# Extension_CN.net
KiCad netlist of a schematic drawn in Altium Designer
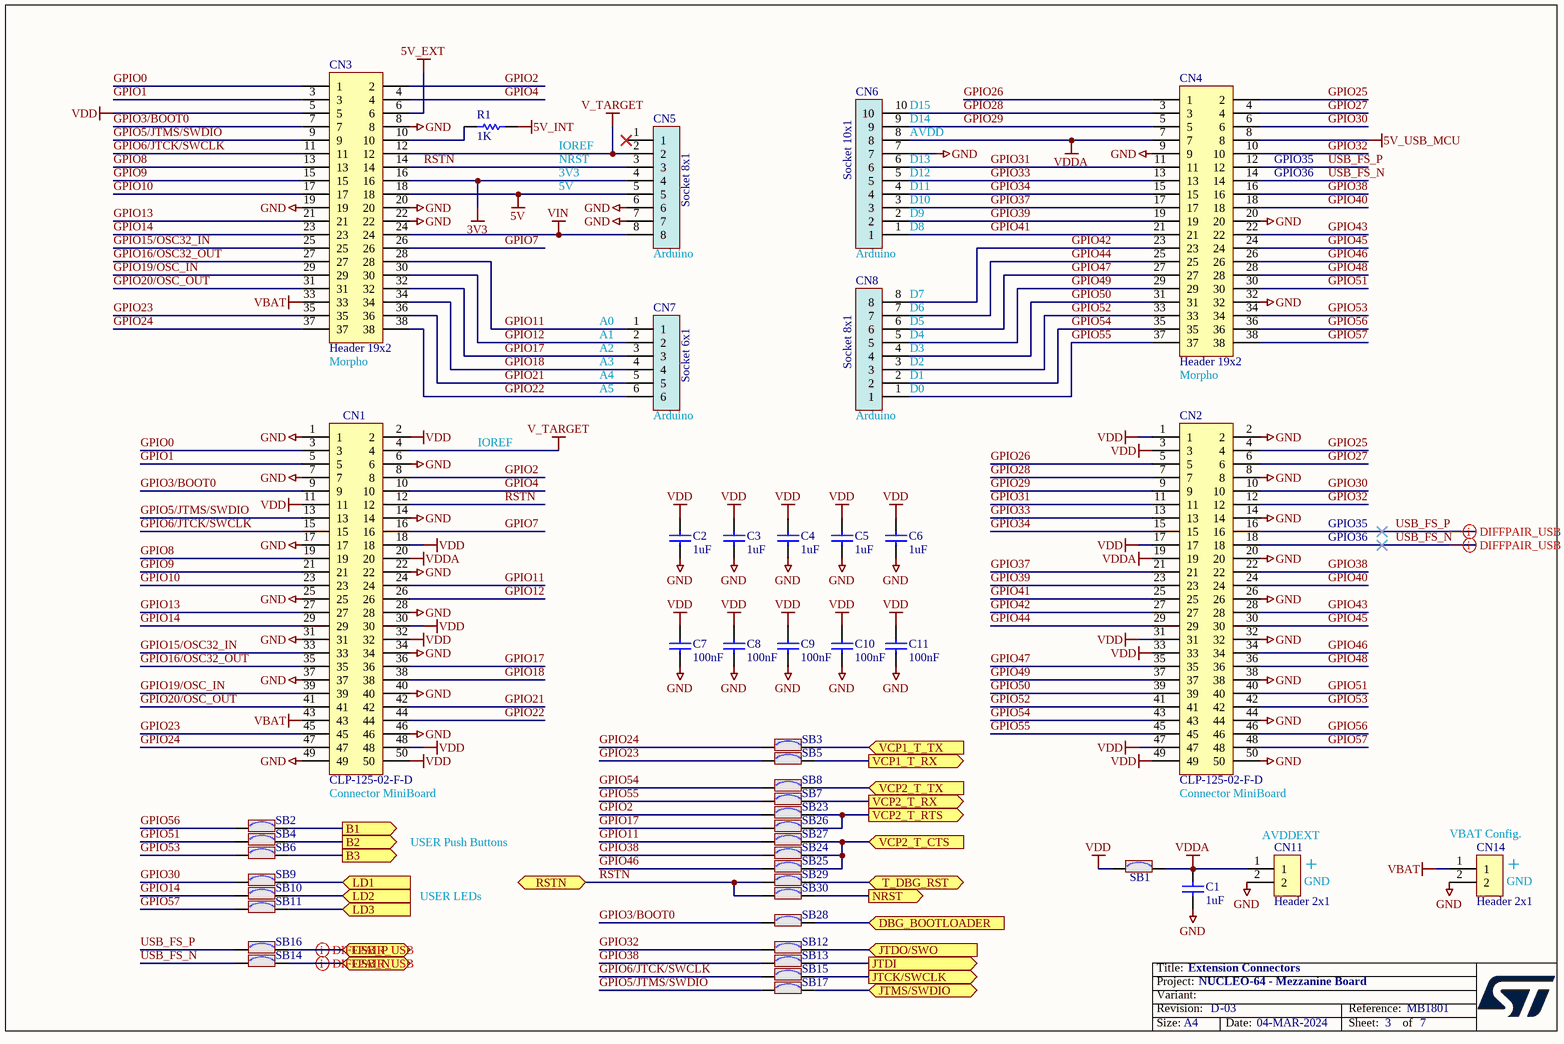
[diagram p0: Extension_CN.SchDoc]

(export (version "E")
  (design (tool "Eeschema 10.0.6"))
  (components
    (comp (ref "C1")
      (value "1uF")
      (footprint "MCD_PARTS:C0805_H0P85")
      (description "Capacitor, MLCC, 1uF, 16V, X5R, +/-10%, 0805, T=0.85mm")
      (fields
        (field (name "INTERNAL_PART_NUMBER") "MCD-01550")
        (field (name "MANUFACTURER_PART_NUMBER") "CC0805KRX5R7BB105")
      )
      (libsource (lib "MCD_PARTS_database") (part "Capacitor"))
    )
    (comp (ref "C2")
      (value "1uF")
      (footprint "MCD_PARTS:C0805_H0P85")
      (description "Capacitor, MLCC, 1uF, 16V, X5R, +/-10%, 0805, T=0.85mm")
      (fields
        (field (name "INTERNAL_PART_NUMBER") "MCD-01550")
        (field (name "MANUFACTURER_PART_NUMBER") "CC0805KRX5R7BB105")
      )
      (libsource (lib "MCD_PARTS_database") (part "Capacitor"))
    )
    (comp (ref "C3")
      (value "1uF")
      (footprint "MCD_PARTS:C0805_H0P85")
      (description "Capacitor, MLCC, 1uF, 16V, X5R, +/-10%, 0805, T=0.85mm")
      (fields
        (field (name "INTERNAL_PART_NUMBER") "MCD-01550")
        (field (name "MANUFACTURER_PART_NUMBER") "CC0805KRX5R7BB105")
      )
      (libsource (lib "MCD_PARTS_database") (part "Capacitor"))
    )
    (comp (ref "C4")
      (value "1uF")
      (footprint "MCD_PARTS:C0805_H0P85")
      (description "Capacitor, MLCC, 1uF, 16V, X5R, +/-10%, 0805, T=0.85mm")
      (fields
        (field (name "INTERNAL_PART_NUMBER") "MCD-01550")
        (field (name "MANUFACTURER_PART_NUMBER") "CC0805KRX5R7BB105")
      )
      (libsource (lib "MCD_PARTS_database") (part "Capacitor"))
    )
    (comp (ref "C5")
      (value "1uF")
      (footprint "MCD_PARTS:C0805_H0P85")
      (description "Capacitor, MLCC, 1uF, 16V, X5R, +/-10%, 0805, T=0.85mm")
      (fields
        (field (name "INTERNAL_PART_NUMBER") "MCD-01550")
        (field (name "MANUFACTURER_PART_NUMBER") "CC0805KRX5R7BB105")
      )
      (libsource (lib "MCD_PARTS_database") (part "Capacitor"))
    )
    (comp (ref "C6")
      (value "1uF")
      (footprint "MCD_PARTS:C0805_H0P85")
      (description "Capacitor, MLCC, 1uF, 16V, X5R, +/-10%, 0805, T=0.85mm")
      (fields
        (field (name "INTERNAL_PART_NUMBER") "MCD-01550")
        (field (name "MANUFACTURER_PART_NUMBER") "CC0805KRX5R7BB105")
      )
      (libsource (lib "MCD_PARTS_database") (part "Capacitor"))
    )
    (comp (ref "C7")
      (value "100nF")
      (footprint "MCD_PARTS:C0402")
      (description "Capacitor, MLCC, 100nF, 25V, X7R, +/-10%, 0402, T=0.5mm")
      (fields (field (name "INTERNAL_PART_NUMBER") "MCD-02355") (field (name "MANUFACTURER") "WALSIN"))
      (libsource (lib "MCD_PARTS_database") (part "Capacitor"))
    )
    (comp (ref "C8")
      (value "100nF")
      (footprint "MCD_PARTS:C0402")
      (description "Capacitor, MLCC, 100nF, 25V, X7R, +/-10%, 0402, T=0.5mm")
      (fields (field (name "INTERNAL_PART_NUMBER") "MCD-02355") (field (name "MANUFACTURER") "WALSIN"))
      (libsource (lib "MCD_PARTS_database") (part "Capacitor"))
    )
    (comp (ref "C9")
      (value "100nF")
      (footprint "MCD_PARTS:C0402")
      (description "Capacitor, MLCC, 100nF, 25V, X7R, +/-10%, 0402, T=0.5mm")
      (fields (field (name "INTERNAL_PART_NUMBER") "MCD-02355") (field (name "MANUFACTURER") "WALSIN"))
      (libsource (lib "MCD_PARTS_database") (part "Capacitor"))
    )
    (comp (ref "C10")
      (value "100nF")
      (footprint "MCD_PARTS:C0402")
      (description "Capacitor, MLCC, 100nF, 25V, X7R, +/-10%, 0402, T=0.5mm")
      (fields (field (name "INTERNAL_PART_NUMBER") "MCD-02355") (field (name "MANUFACTURER") "WALSIN"))
      (libsource (lib "MCD_PARTS_database") (part "Capacitor"))
    )
    (comp (ref "C11")
      (value "100nF")
      (footprint "MCD_PARTS:C0402")
      (description "Capacitor, MLCC, 100nF, 25V, X7R, +/-10%, 0402, T=0.5mm")
      (fields (field (name "INTERNAL_PART_NUMBER") "MCD-02355") (field (name "MANUFACTURER") "WALSIN"))
      (libsource (lib "MCD_PARTS_database") (part "Capacitor"))
    )
    (comp (ref "CN1")
      (value "CLP-125-02-F-D")
      (footprint "MCD_PARTS:CON_SAMTEC_CLP-125-02-F-D")
      (description "Socket, 25x2, 1.27mm, VR, SMD, T=2.29mm")
      (fields (field (name "INTERNAL_PART_NUMBER") "MCD-02705") (field (name "MANUFACTURER") "SAMTEC"))
      (libsource (lib "MCD_PARTS_database") (part "CLP-125-02-F-D"))
    )
    (comp (ref "CN2")
      (value "CLP-125-02-F-D")
      (footprint "MCD_PARTS:CON_SAMTEC_CLP-125-02-F-D")
      (description "Socket, 25x2, 1.27mm, VR, SMD, T=2.29mm")
      (fields (field (name "INTERNAL_PART_NUMBER") "MCD-02705") (field (name "MANUFACTURER") "SAMTEC"))
      (libsource (lib "MCD_PARTS_database") (part "CLP-125-02-F-D"))
    )
    (comp (ref "CN3")
      (value "Header 19x2")
      (footprint "MCD_PARTS:CON_SAMTEC_TSW-119-09-X-D")
      (description "Header, 19x2, 2.54mm, VR, TH, T=5.84mm/10.16mm")
      (fields (field (name "INTERNAL_PART_NUMBER") "MCD-00213") (field (name "MANUFACTURER") "SAMTEC"))
      (libsource (lib "MCD_PARTS_database") (part "Header 19x2"))
    )
    (comp (ref "CN4")
      (value "Header 19x2")
      (footprint "MCD_PARTS:CON_SAMTEC_TSW-119-09-X-D")
      (description "Header, 19x2, 2.54mm, VR, TH, T=5.84mm/10.16mm")
      (fields (field (name "INTERNAL_PART_NUMBER") "MCD-00213") (field (name "MANUFACTURER") "SAMTEC"))
      (libsource (lib "MCD_PARTS_database") (part "Header 19x2"))
    )
    (comp (ref "CN5")
      (value "Socket 8x1")
      (footprint "MCD_PARTS:CON_SAMTEC_SSW-108-01-X-S")
      (description "Socket, 8x1, 2.54mm, VR, TH, T=8.51/2.64mm")
      (fields (field (name "INTERNAL_PART_NUMBER") "MCD-01743") (field (name "MANUFACTURER") "SAMTEC"))
      (libsource (lib "") (part "Socket 8x1_1"))
    )
    (comp (ref "CN6")
      (value "Socket 10x1")
      (footprint "MCD_PARTS:CON_SAMTEC_SSW-110-01-X-S")
      (description "Socket, 10x1, 2.54mm, VR, TH, T=8.51/2.64mm")
      (fields (field (name "INTERNAL_PART_NUMBER") "MCD-02080") (field (name "MANUFACTURER") "SAMTEC"))
      (libsource (lib "MCD_PARTS_database") (part "Socket 10x1"))
    )
    (comp (ref "CN7")
      (value "Socket 6x1")
      (footprint "MCD_PARTS:CON_SAMTEC_SSW-106-01-X-S")
      (description "Socket, 6x1, 2.54mm, VR, TH, T=8.51/2.64mm")
      (fields (field (name "INTERNAL_PART_NUMBER") "MCD-02079") (field (name "MANUFACTURER") "SAMTEC"))
      (libsource (lib "MCD_PARTS_database") (part "Socket 6x1"))
    )
    (comp (ref "CN8")
      (value "Socket 8x1")
      (footprint "MCD_PARTS:CON_SAMTEC_SSW-108-01-X-S")
      (description "Socket, 8x1, 2.54mm, VR, TH, T=8.51/2.64mm")
      (fields (field (name "INTERNAL_PART_NUMBER") "MCD-01743") (field (name "MANUFACTURER") "SAMTEC"))
      (libsource (lib "MCD_PARTS_database") (part "Socket 8x1"))
    )
    (comp (ref "CN11")
      (value "Header 2x1")
      (footprint "MCD_PARTS:CON_SAMTEC_TSW-102-07-G-S")
      (description "Header, 2x1, 2.54mm, VR, TH, T=5.84mm/2.54mm")
      (fields (field (name "INTERNAL_PART_NUMBER") "MCD-00032") (field (name "MANUFACTURER") "SAMTEC"))
      (libsource (lib "MCD_PARTS_database") (part "Header 2x1"))
    )
    (comp (ref "CN14")
      (value "Header 2x1")
      (footprint "MCD_PARTS:CON_SAMTEC_TSW-102-07-G-S")
      (description "Header, 2x1, 2.54mm, VR, TH, T=5.84mm/2.54mm")
      (fields (field (name "INTERNAL_PART_NUMBER") "MCD-00032") (field (name "MANUFACTURER") "SAMTEC"))
      (libsource (lib "MCD_PARTS_database") (part "Header 2x1"))
    )
    (comp (ref "R1")
      (value "1K")
      (footprint "MCD_PARTS:R0402")
      (description "Resistor, 1K, 0402, +/-1%,1/16W")
      (fields (field (name "INTERNAL_PART_NUMBER") "MCD-00061") (field (name "MANUFACTURER") "YAGEO"))
      (libsource (lib "MCD_PARTS_database") (part "Resistor"))
    )
    (comp (ref "SB1")
      (value "SB_ON")
      (footprint "MCD_PARTS:SOLDER-BRIDGE_R0402-0R")
      (description "Solder Bridge 0402 ON")
      (fields (field (name "INTERNAL_PART_NUMBER") "MCD-01618") (field (name "MANUFACTURER") "YAGEO"))
      (libsource (lib "MCD_PARTS_database") (part "SB_ON"))
    )
    (comp (ref "SB2")
      (value "SB_ON")
      (footprint "MCD_PARTS:SOLDER-BRIDGE_R0402-0R")
      (description "Solder Bridge 0402 ON")
      (fields (field (name "INTERNAL_PART_NUMBER") "MCD-01618") (field (name "MANUFACTURER") "YAGEO"))
      (libsource (lib "MCD_PARTS_database") (part "SB_ON"))
    )
    (comp (ref "SB3")
      (value "SB_ON")
      (footprint "MCD_PARTS:SOLDER-BRIDGE_R0402-0R")
      (description "Solder Bridge 0402 ON")
      (fields (field (name "INTERNAL_PART_NUMBER") "MCD-01618") (field (name "MANUFACTURER") "YAGEO"))
      (libsource (lib "MCD_PARTS_database") (part "SB_ON"))
    )
    (comp (ref "SB4")
      (value "SB_ON")
      (footprint "MCD_PARTS:SOLDER-BRIDGE_R0402-0R")
      (description "Solder Bridge 0402 ON")
      (fields (field (name "INTERNAL_PART_NUMBER") "MCD-01618") (field (name "MANUFACTURER") "YAGEO"))
      (libsource (lib "MCD_PARTS_database") (part "SB_ON"))
    )
    (comp (ref "SB5")
      (value "SB_ON")
      (footprint "MCD_PARTS:SOLDER-BRIDGE_R0402-0R")
      (description "Solder Bridge 0402 ON")
      (fields (field (name "INTERNAL_PART_NUMBER") "MCD-01618") (field (name "MANUFACTURER") "YAGEO"))
      (libsource (lib "MCD_PARTS_database") (part "SB_ON"))
    )
    (comp (ref "SB6")
      (value "SB_ON")
      (footprint "MCD_PARTS:SOLDER-BRIDGE_R0402-0R")
      (description "Solder Bridge 0402 ON")
      (fields (field (name "INTERNAL_PART_NUMBER") "MCD-01618") (field (name "MANUFACTURER") "YAGEO"))
      (libsource (lib "MCD_PARTS_database") (part "SB_ON"))
    )
    (comp (ref "SB7")
      (value "SB_ON")
      (footprint "MCD_PARTS:SOLDER-BRIDGE_R0402-0R")
      (description "Solder Bridge 0402 ON")
      (fields (field (name "INTERNAL_PART_NUMBER") "MCD-01618") (field (name "MANUFACTURER") "YAGEO"))
      (libsource (lib "MCD_PARTS_database") (part "SB_ON"))
    )
    (comp (ref "SB8")
      (value "SB_ON")
      (footprint "MCD_PARTS:SOLDER-BRIDGE_R0402-0R")
      (description "Solder Bridge 0402 ON")
      (fields (field (name "INTERNAL_PART_NUMBER") "MCD-01618") (field (name "MANUFACTURER") "YAGEO"))
      (libsource (lib "MCD_PARTS_database") (part "SB_ON"))
    )
    (comp (ref "SB9")
      (value "SB_ON")
      (footprint "MCD_PARTS:SOLDER-BRIDGE_R0402-0R")
      (description "Solder Bridge 0402 ON")
      (fields (field (name "INTERNAL_PART_NUMBER") "MCD-01618") (field (name "MANUFACTURER") "YAGEO"))
      (libsource (lib "MCD_PARTS_database") (part "SB_ON"))
    )
    (comp (ref "SB10")
      (value "SB_ON")
      (footprint "MCD_PARTS:SOLDER-BRIDGE_R0402-0R")
      (description "Solder Bridge 0402 ON")
      (fields (field (name "INTERNAL_PART_NUMBER") "MCD-01618") (field (name "MANUFACTURER") "YAGEO"))
      (libsource (lib "MCD_PARTS_database") (part "SB_ON"))
    )
    (comp (ref "SB11")
      (value "SB_ON")
      (footprint "MCD_PARTS:SOLDER-BRIDGE_R0402-0R")
      (description "Solder Bridge 0402 ON")
      (fields (field (name "INTERNAL_PART_NUMBER") "MCD-01618") (field (name "MANUFACTURER") "YAGEO"))
      (libsource (lib "MCD_PARTS_database") (part "SB_ON"))
    )
    (comp (ref "SB12")
      (value "SB_ON")
      (footprint "MCD_PARTS:SOLDER-BRIDGE_R0402-0R")
      (description "Solder Bridge 0402 ON")
      (fields (field (name "INTERNAL_PART_NUMBER") "MCD-01618") (field (name "MANUFACTURER") "YAGEO"))
      (libsource (lib "MCD_PARTS_database") (part "SB_ON"))
    )
    (comp (ref "SB13")
      (value "SB_ON")
      (footprint "MCD_PARTS:SOLDER-BRIDGE_R0402-0R")
      (description "Solder Bridge 0402 ON")
      (fields (field (name "INTERNAL_PART_NUMBER") "MCD-01618") (field (name "MANUFACTURER") "YAGEO"))
      (libsource (lib "MCD_PARTS_database") (part "SB_ON"))
    )
    (comp (ref "SB14")
      (value "SB_ON")
      (footprint "MCD_PARTS:SOLDER-BRIDGE_R0402-0R")
      (description "Solder Bridge 0402 ON")
      (fields (field (name "INTERNAL_PART_NUMBER") "MCD-01618") (field (name "MANUFACTURER") "YAGEO"))
      (libsource (lib "MCD_PARTS_database") (part "SB_ON"))
    )
    (comp (ref "SB15")
      (value "SB_ON")
      (footprint "MCD_PARTS:SOLDER-BRIDGE_R0402-0R")
      (description "Solder Bridge 0402 ON")
      (fields (field (name "INTERNAL_PART_NUMBER") "MCD-01618") (field (name "MANUFACTURER") "YAGEO"))
      (libsource (lib "MCD_PARTS_database") (part "SB_ON"))
    )
    (comp (ref "SB16")
      (value "SB_ON")
      (footprint "MCD_PARTS:SOLDER-BRIDGE_R0402-0R")
      (description "Solder Bridge 0402 ON")
      (fields (field (name "INTERNAL_PART_NUMBER") "MCD-01618") (field (name "MANUFACTURER") "YAGEO"))
      (libsource (lib "MCD_PARTS_database") (part "SB_ON"))
    )
    (comp (ref "SB17")
      (value "SB_ON")
      (footprint "MCD_PARTS:SOLDER-BRIDGE_R0402-0R")
      (description "Solder Bridge 0402 ON")
      (fields (field (name "INTERNAL_PART_NUMBER") "MCD-01618") (field (name "MANUFACTURER") "YAGEO"))
      (libsource (lib "MCD_PARTS_database") (part "SB_ON"))
    )
    (comp (ref "SB23")
      (value "SB_ON")
      (footprint "MCD_PARTS:SOLDER-BRIDGE_R0402-0R")
      (description "Solder Bridge 0402 ON")
      (fields (field (name "INTERNAL_PART_NUMBER") "MCD-01618") (field (name "MANUFACTURER") "YAGEO"))
      (libsource (lib "MCD_PARTS_database") (part "SB_ON"))
    )
    (comp (ref "SB24")
      (value "SB_ON")
      (footprint "MCD_PARTS:SOLDER-BRIDGE_R0402-0R")
      (description "Solder Bridge 0402 ON")
      (fields (field (name "INTERNAL_PART_NUMBER") "MCD-01618") (field (name "MANUFACTURER") "YAGEO"))
      (libsource (lib "MCD_PARTS_database") (part "SB_ON"))
    )
    (comp (ref "SB25")
      (value "SB_ON")
      (footprint "MCD_PARTS:SOLDER-BRIDGE_R0402-0R")
      (description "Solder Bridge 0402 ON")
      (fields (field (name "INTERNAL_PART_NUMBER") "MCD-01618") (field (name "MANUFACTURER") "YAGEO"))
      (libsource (lib "MCD_PARTS_database") (part "SB_ON"))
    )
    (comp (ref "SB26")
      (value "SB_ON")
      (footprint "MCD_PARTS:SOLDER-BRIDGE_R0402-0R")
      (description "Solder Bridge 0402 ON")
      (fields (field (name "INTERNAL_PART_NUMBER") "MCD-01618") (field (name "MANUFACTURER") "YAGEO"))
      (libsource (lib "MCD_PARTS_database") (part "SB_ON"))
    )
    (comp (ref "SB27")
      (value "SB_ON")
      (footprint "MCD_PARTS:SOLDER-BRIDGE_R0402-0R")
      (description "Solder Bridge 0402 ON")
      (fields (field (name "INTERNAL_PART_NUMBER") "MCD-01618") (field (name "MANUFACTURER") "YAGEO"))
      (libsource (lib "MCD_PARTS_database") (part "SB_ON"))
    )
    (comp (ref "SB28")
      (value "SB_ON")
      (footprint "SOLDER-BRIDGE_R0402-0R")
      (description "Solder Bridge 0402 ON")
      (fields (field (name "INTERNAL_PART_NUMBER") "MCD-01618") (field (name "MANUFACTURER") "YAGEO"))
      (libsource (lib "MCD_PARTS_database") (part "SB_ON"))
    )
    (comp (ref "SB29")
      (value "SB_ON")
      (footprint "SOLDER-BRIDGE_R0402-0R")
      (description "Solder Bridge 0402 ON")
      (fields (field (name "INTERNAL_PART_NUMBER") "MCD-01618") (field (name "MANUFACTURER") "YAGEO"))
      (libsource (lib "MCD_PARTS_database") (part "SB_ON"))
    )
    (comp (ref "SB30")
      (value "SB_ON")
      (footprint "SOLDER-BRIDGE_R0402-0R")
      (description "Solder Bridge 0402 ON")
      (fields (field (name "INTERNAL_PART_NUMBER") "MCD-01618") (field (name "MANUFACTURER") "YAGEO"))
      (libsource (lib "MCD_PARTS_database") (part "SB_ON"))
    )
  )
  (nets
    (net (code "1") (name "/B1") (class "Default")
      (node (ref "SB2") (pin "2") (pinfunction "2_2") (pintype "passive"))
    )
    (net (code "2") (name "/B2") (class "Default")
      (node (ref "SB4") (pin "2") (pinfunction "2_2") (pintype "passive"))
    )
    (net (code "3") (name "/B3") (class "Default")
      (node (ref "SB6") (pin "2") (pinfunction "2_2") (pintype "passive"))
    )
    (net (code "4") (name "/DBG_BOOTLOADER") (class "Default")
      (node (ref "SB28") (pin "2") (pinfunction "2_2") (pintype "passive"))
    )
    (net (code "5") (name "/GPIO0") (class "Default")
      (node (ref "CN1") (pin "3") (pinfunction "3_3") (pintype "passive"))
      (node (ref "CN3") (pin "1") (pinfunction "1_1") (pintype "passive"))
    )
    (net (code "6") (name "/GPIO1") (class "Default")
      (node (ref "CN1") (pin "5") (pinfunction "5_5") (pintype "passive"))
      (node (ref "CN3") (pin "3") (pinfunction "3_3") (pintype "passive"))
    )
    (net (code "7") (name "/GPIO2") (class "Default")
      (node (ref "CN1") (pin "8") (pinfunction "8_8") (pintype "passive"))
      (node (ref "CN3") (pin "2") (pinfunction "2_2") (pintype "passive"))
      (node (ref "SB23") (pin "1") (pinfunction "1_1") (pintype "passive"))
    )
    (net (code "8") (name "/GPIO3{slash}BOOT0") (class "Default")
      (node (ref "CN1") (pin "9") (pinfunction "9_9") (pintype "passive"))
      (node (ref "CN3") (pin "7") (pinfunction "7_7") (pintype "passive"))
      (node (ref "SB28") (pin "1") (pinfunction "1_1") (pintype "passive"))
    )
    (net (code "9") (name "/GPIO4") (class "Default")
      (node (ref "CN1") (pin "10") (pinfunction "10_10") (pintype "passive"))
      (node (ref "CN3") (pin "4") (pinfunction "4_4") (pintype "passive"))
    )
    (net (code "10") (name "/GPIO5{slash}JTMS{slash}SWDIO") (class "Default")
      (node (ref "CN1") (pin "13") (pinfunction "13_13") (pintype "passive"))
      (node (ref "CN3") (pin "9") (pinfunction "9_9") (pintype "passive"))
      (node (ref "SB17") (pin "1") (pinfunction "1_1") (pintype "passive"))
    )
    (net (code "11") (name "/GPIO6{slash}JTCK{slash}SWCLK") (class "Default")
      (node (ref "CN1") (pin "15") (pinfunction "15_15") (pintype "passive"))
      (node (ref "CN3") (pin "11") (pinfunction "11_11") (pintype "passive"))
      (node (ref "SB15") (pin "1") (pinfunction "1_1") (pintype "passive"))
    )
    (net (code "12") (name "/GPIO7") (class "Default")
      (node (ref "CN1") (pin "16") (pinfunction "16_16") (pintype "passive"))
      (node (ref "CN3") (pin "26") (pinfunction "26_26") (pintype "passive"))
    )
    (net (code "13") (name "/GPIO8") (class "Default")
      (node (ref "CN1") (pin "19") (pinfunction "19_19") (pintype "passive"))
      (node (ref "CN3") (pin "13") (pinfunction "13_13") (pintype "passive"))
    )
    (net (code "14") (name "/GPIO9") (class "Default")
      (node (ref "CN1") (pin "21") (pinfunction "21_21") (pintype "passive"))
      (node (ref "CN3") (pin "15") (pinfunction "15_15") (pintype "passive"))
    )
    (net (code "15") (name "/GPIO10") (class "Default")
      (node (ref "CN1") (pin "23") (pinfunction "23_23") (pintype "passive"))
      (node (ref "CN3") (pin "17") (pinfunction "17_17") (pintype "passive"))
    )
    (net (code "16") (name "/GPIO11") (class "Default")
      (node (ref "CN1") (pin "24") (pinfunction "24_24") (pintype "passive"))
      (node (ref "CN3") (pin "28") (pinfunction "28_28") (pintype "passive"))
      (node (ref "CN7") (pin "1") (pinfunction "1_1") (pintype "passive"))
      (node (ref "SB27") (pin "1") (pinfunction "1_1") (pintype "passive"))
    )
    (net (code "17") (name "/GPIO12") (class "Default")
      (node (ref "CN1") (pin "26") (pinfunction "26_26") (pintype "passive"))
      (node (ref "CN3") (pin "30") (pinfunction "30_30") (pintype "passive"))
      (node (ref "CN7") (pin "2") (pinfunction "2_2") (pintype "passive"))
    )
    (net (code "18") (name "/GPIO13") (class "Default")
      (node (ref "CN1") (pin "27") (pinfunction "27_27") (pintype "passive"))
      (node (ref "CN3") (pin "21") (pinfunction "21_21") (pintype "passive"))
    )
    (net (code "19") (name "/GPIO14") (class "Default")
      (node (ref "CN1") (pin "29") (pinfunction "29_29") (pintype "passive"))
      (node (ref "CN3") (pin "23") (pinfunction "23_23") (pintype "passive"))
      (node (ref "SB10") (pin "1") (pinfunction "1_1") (pintype "passive"))
    )
    (net (code "20") (name "/GPIO15{slash}OSC32_IN") (class "Default")
      (node (ref "CN1") (pin "33") (pinfunction "33_33") (pintype "passive"))
      (node (ref "CN3") (pin "25") (pinfunction "25_25") (pintype "passive"))
    )
    (net (code "21") (name "/GPIO16{slash}OSC32_OUT") (class "Default")
      (node (ref "CN1") (pin "35") (pinfunction "35_35") (pintype "passive"))
      (node (ref "CN3") (pin "27") (pinfunction "27_27") (pintype "passive"))
    )
    (net (code "22") (name "/GPIO17") (class "Default")
      (node (ref "CN1") (pin "36") (pinfunction "36_36") (pintype "passive"))
      (node (ref "CN3") (pin "32") (pinfunction "32_32") (pintype "passive"))
      (node (ref "CN7") (pin "3") (pinfunction "3_3") (pintype "passive"))
      (node (ref "SB26") (pin "1") (pinfunction "1_1") (pintype "passive"))
    )
    (net (code "23") (name "/GPIO18") (class "Default")
      (node (ref "CN1") (pin "38") (pinfunction "38_38") (pintype "passive"))
      (node (ref "CN3") (pin "34") (pinfunction "34_34") (pintype "passive"))
      (node (ref "CN7") (pin "4") (pinfunction "4_4") (pintype "passive"))
    )
    (net (code "24") (name "/GPIO19{slash}OSC_IN") (class "Default")
      (node (ref "CN1") (pin "39") (pinfunction "39_39") (pintype "passive"))
      (node (ref "CN3") (pin "29") (pinfunction "29_29") (pintype "passive"))
    )
    (net (code "25") (name "/GPIO20{slash}OSC_OUT") (class "Default")
      (node (ref "CN1") (pin "41") (pinfunction "41_41") (pintype "passive"))
      (node (ref "CN3") (pin "31") (pinfunction "31_31") (pintype "passive"))
    )
    (net (code "26") (name "/GPIO21") (class "Default")
      (node (ref "CN1") (pin "42") (pinfunction "42_42") (pintype "passive"))
      (node (ref "CN3") (pin "36") (pinfunction "36_36") (pintype "passive"))
      (node (ref "CN7") (pin "5") (pinfunction "5_5") (pintype "passive"))
    )
    (net (code "27") (name "/GPIO22") (class "Default")
      (node (ref "CN1") (pin "44") (pinfunction "44_44") (pintype "passive"))
      (node (ref "CN3") (pin "38") (pinfunction "38_38") (pintype "passive"))
      (node (ref "CN7") (pin "6") (pinfunction "6_6") (pintype "passive"))
    )
    (net (code "28") (name "/GPIO23") (class "Default")
      (node (ref "CN1") (pin "45") (pinfunction "45_45") (pintype "passive"))
      (node (ref "CN3") (pin "35") (pinfunction "35_35") (pintype "passive"))
      (node (ref "SB5") (pin "1") (pinfunction "1_1") (pintype "passive"))
    )
    (net (code "29") (name "/GPIO24") (class "Default")
      (node (ref "CN1") (pin "47") (pinfunction "47_47") (pintype "passive"))
      (node (ref "CN3") (pin "37") (pinfunction "37_37") (pintype "passive"))
      (node (ref "SB3") (pin "1") (pinfunction "1_1") (pintype "passive"))
    )
    (net (code "30") (name "/GPIO25") (class "Default")
      (node (ref "CN2") (pin "4") (pinfunction "4_4") (pintype "passive"))
      (node (ref "CN4") (pin "2") (pinfunction "2_2") (pintype "passive"))
    )
    (net (code "31") (name "/GPIO26") (class "Default")
      (node (ref "CN2") (pin "5") (pinfunction "5_5") (pintype "passive"))
      (node (ref "CN4") (pin "1") (pinfunction "1_1") (pintype "passive"))
    )
    (net (code "32") (name "/GPIO27") (class "Default")
      (node (ref "CN2") (pin "6") (pinfunction "6_6") (pintype "passive"))
      (node (ref "CN4") (pin "4") (pinfunction "4_4") (pintype "passive"))
    )
    (net (code "33") (name "/GPIO28") (class "Default")
      (node (ref "CN2") (pin "7") (pinfunction "7_7") (pintype "passive"))
      (node (ref "CN4") (pin "3") (pinfunction "3_3") (pintype "passive"))
      (node (ref "CN6") (pin "10") (pinfunction "10_10") (pintype "passive"))
    )
    (net (code "34") (name "/GPIO29") (class "Default")
      (node (ref "CN2") (pin "9") (pinfunction "9_9") (pintype "passive"))
      (node (ref "CN4") (pin "5") (pinfunction "5_5") (pintype "passive"))
      (node (ref "CN6") (pin "9") (pinfunction "9_9") (pintype "passive"))
    )
    (net (code "35") (name "/GPIO30") (class "Default")
      (node (ref "CN2") (pin "10") (pinfunction "10_10") (pintype "passive"))
      (node (ref "CN4") (pin "6") (pinfunction "6_6") (pintype "passive"))
      (node (ref "SB9") (pin "1") (pinfunction "1_1") (pintype "passive"))
    )
    (net (code "36") (name "/GPIO31") (class "Default")
      (node (ref "CN2") (pin "11") (pinfunction "11_11") (pintype "passive"))
      (node (ref "CN4") (pin "11") (pinfunction "11_11") (pintype "passive"))
      (node (ref "CN6") (pin "6") (pinfunction "6_6") (pintype "passive"))
    )
    (net (code "37") (name "/GPIO32") (class "Default")
      (node (ref "CN2") (pin "12") (pinfunction "12_12") (pintype "passive"))
      (node (ref "CN4") (pin "10") (pinfunction "10_10") (pintype "passive"))
      (node (ref "SB12") (pin "1") (pinfunction "1_1") (pintype "passive"))
    )
    (net (code "38") (name "/GPIO33") (class "Default")
      (node (ref "CN2") (pin "13") (pinfunction "13_13") (pintype "passive"))
      (node (ref "CN4") (pin "13") (pinfunction "13_13") (pintype "passive"))
      (node (ref "CN6") (pin "5") (pinfunction "5_5") (pintype "passive"))
    )
    (net (code "39") (name "/GPIO34") (class "Default")
      (node (ref "CN2") (pin "15") (pinfunction "15_15") (pintype "passive"))
      (node (ref "CN4") (pin "15") (pinfunction "15_15") (pintype "passive"))
      (node (ref "CN6") (pin "4") (pinfunction "4_4") (pintype "passive"))
    )
    (net (code "40") (name "/GPIO37") (class "Default")
      (node (ref "CN2") (pin "21") (pinfunction "21_21") (pintype "passive"))
      (node (ref "CN4") (pin "17") (pinfunction "17_17") (pintype "passive"))
      (node (ref "CN6") (pin "3") (pinfunction "3_3") (pintype "passive"))
    )
    (net (code "41") (name "/GPIO38") (class "Default")
      (node (ref "CN2") (pin "22") (pinfunction "22_22") (pintype "passive"))
      (node (ref "CN4") (pin "16") (pinfunction "16_16") (pintype "passive"))
      (node (ref "SB13") (pin "1") (pinfunction "1_1") (pintype "passive"))
      (node (ref "SB24") (pin "1") (pinfunction "1_1") (pintype "passive"))
    )
    (net (code "42") (name "/GPIO39") (class "Default")
      (node (ref "CN2") (pin "23") (pinfunction "23_23") (pintype "passive"))
      (node (ref "CN4") (pin "19") (pinfunction "19_19") (pintype "passive"))
      (node (ref "CN6") (pin "2") (pinfunction "2_2") (pintype "passive"))
    )
    (net (code "43") (name "/GPIO40") (class "Default")
      (node (ref "CN2") (pin "24") (pinfunction "24_24") (pintype "passive"))
      (node (ref "CN4") (pin "18") (pinfunction "18_18") (pintype "passive"))
    )
    (net (code "44") (name "/GPIO41") (class "Default")
      (node (ref "CN2") (pin "25") (pinfunction "25_25") (pintype "passive"))
      (node (ref "CN4") (pin "21") (pinfunction "21_21") (pintype "passive"))
      (node (ref "CN6") (pin "1") (pinfunction "1_1") (pintype "passive"))
    )
    (net (code "45") (name "/GPIO42") (class "Default")
      (node (ref "CN2") (pin "27") (pinfunction "27_27") (pintype "passive"))
      (node (ref "CN4") (pin "23") (pinfunction "23_23") (pintype "passive"))
      (node (ref "CN8") (pin "8") (pinfunction "8_8") (pintype "passive"))
    )
    (net (code "46") (name "/GPIO43") (class "Default")
      (node (ref "CN2") (pin "28") (pinfunction "28_28") (pintype "passive"))
      (node (ref "CN4") (pin "22") (pinfunction "22_22") (pintype "passive"))
    )
    (net (code "47") (name "/GPIO44") (class "Default")
      (node (ref "CN2") (pin "29") (pinfunction "29_29") (pintype "passive"))
      (node (ref "CN4") (pin "25") (pinfunction "25_25") (pintype "passive"))
      (node (ref "CN8") (pin "7") (pinfunction "7_7") (pintype "passive"))
    )
    (net (code "48") (name "/GPIO45") (class "Default")
      (node (ref "CN2") (pin "30") (pinfunction "30_30") (pintype "passive"))
      (node (ref "CN4") (pin "24") (pinfunction "24_24") (pintype "passive"))
    )
    (net (code "49") (name "/GPIO46") (class "Default")
      (node (ref "CN2") (pin "34") (pinfunction "34_34") (pintype "passive"))
      (node (ref "CN4") (pin "26") (pinfunction "26_26") (pintype "passive"))
      (node (ref "SB25") (pin "1") (pinfunction "1_1") (pintype "passive"))
    )
    (net (code "50") (name "/GPIO47") (class "Default")
      (node (ref "CN2") (pin "35") (pinfunction "35_35") (pintype "passive"))
      (node (ref "CN4") (pin "27") (pinfunction "27_27") (pintype "passive"))
      (node (ref "CN8") (pin "6") (pinfunction "6_6") (pintype "passive"))
    )
    (net (code "51") (name "/GPIO48") (class "Default")
      (node (ref "CN2") (pin "36") (pinfunction "36_36") (pintype "passive"))
      (node (ref "CN4") (pin "28") (pinfunction "28_28") (pintype "passive"))
    )
    (net (code "52") (name "/GPIO49") (class "Default")
      (node (ref "CN2") (pin "37") (pinfunction "37_37") (pintype "passive"))
      (node (ref "CN4") (pin "29") (pinfunction "29_29") (pintype "passive"))
      (node (ref "CN8") (pin "5") (pinfunction "5_5") (pintype "passive"))
    )
    (net (code "53") (name "/GPIO50") (class "Default")
      (node (ref "CN2") (pin "39") (pinfunction "39_39") (pintype "passive"))
      (node (ref "CN4") (pin "31") (pinfunction "31_31") (pintype "passive"))
      (node (ref "CN8") (pin "4") (pinfunction "4_4") (pintype "passive"))
    )
    (net (code "54") (name "/GPIO51") (class "Default")
      (node (ref "CN2") (pin "40") (pinfunction "40_40") (pintype "passive"))
      (node (ref "CN4") (pin "30") (pinfunction "30_30") (pintype "passive"))
      (node (ref "SB4") (pin "1") (pinfunction "1_1") (pintype "passive"))
    )
    (net (code "55") (name "/GPIO52") (class "Default")
      (node (ref "CN2") (pin "41") (pinfunction "41_41") (pintype "passive"))
      (node (ref "CN4") (pin "33") (pinfunction "33_33") (pintype "passive"))
      (node (ref "CN8") (pin "3") (pinfunction "3_3") (pintype "passive"))
    )
    (net (code "56") (name "/GPIO53") (class "Default")
      (node (ref "CN2") (pin "42") (pinfunction "42_42") (pintype "passive"))
      (node (ref "CN4") (pin "34") (pinfunction "34_34") (pintype "passive"))
      (node (ref "SB6") (pin "1") (pinfunction "1_1") (pintype "passive"))
    )
    (net (code "57") (name "/GPIO54") (class "Default")
      (node (ref "CN2") (pin "43") (pinfunction "43_43") (pintype "passive"))
      (node (ref "CN4") (pin "35") (pinfunction "35_35") (pintype "passive"))
      (node (ref "CN8") (pin "2") (pinfunction "2_2") (pintype "passive"))
      (node (ref "SB8") (pin "1") (pinfunction "1_1") (pintype "passive"))
    )
    (net (code "58") (name "/GPIO55") (class "Default")
      (node (ref "CN2") (pin "45") (pinfunction "45_45") (pintype "passive"))
      (node (ref "CN4") (pin "37") (pinfunction "37_37") (pintype "passive"))
      (node (ref "CN8") (pin "1") (pinfunction "1_1") (pintype "passive"))
      (node (ref "SB7") (pin "1") (pinfunction "1_1") (pintype "passive"))
    )
    (net (code "59") (name "/GPIO56") (class "Default")
      (node (ref "CN2") (pin "46") (pinfunction "46_46") (pintype "passive"))
      (node (ref "CN4") (pin "36") (pinfunction "36_36") (pintype "passive"))
      (node (ref "SB2") (pin "1") (pinfunction "1_1") (pintype "passive"))
    )
    (net (code "60") (name "/GPIO57") (class "Default")
      (node (ref "CN2") (pin "48") (pinfunction "48_48") (pintype "passive"))
      (node (ref "CN4") (pin "38") (pinfunction "38_38") (pintype "passive"))
      (node (ref "SB11") (pin "1") (pinfunction "1_1") (pintype "passive"))
    )
    (net (code "61") (name "/JTCK{slash}SWCLK") (class "Default")
      (node (ref "SB15") (pin "2") (pinfunction "2_2") (pintype "passive"))
    )
    (net (code "62") (name "/JTDI") (class "Default")
      (node (ref "SB13") (pin "2") (pinfunction "2_2") (pintype "passive"))
    )
    (net (code "63") (name "/JTDO{slash}SWO") (class "Default")
      (node (ref "SB12") (pin "2") (pinfunction "2_2") (pintype "passive"))
    )
    (net (code "64") (name "/JTMS{slash}SWDIO") (class "Default")
      (node (ref "SB17") (pin "2") (pinfunction "2_2") (pintype "passive"))
    )
    (net (code "65") (name "/LD1") (class "Default")
      (node (ref "SB9") (pin "2") (pinfunction "2_2") (pintype "passive"))
    )
    (net (code "66") (name "/LD2") (class "Default")
      (node (ref "SB10") (pin "2") (pinfunction "2_2") (pintype "passive"))
    )
    (net (code "67") (name "/LD3") (class "Default")
      (node (ref "SB11") (pin "2") (pinfunction "2_2") (pintype "passive"))
    )
    (net (code "68") (name "/NRST") (class "Default")
      (node (ref "SB30") (pin "2") (pinfunction "2_2") (pintype "passive"))
    )
    (net (code "69") (name "/RSTN") (class "Default")
      (node (ref "CN1") (pin "12") (pinfunction "12_12") (pintype "passive"))
      (node (ref "CN3") (pin "14") (pinfunction "14_14") (pintype "passive"))
      (node (ref "CN5") (pin "3") (pinfunction "3_3") (pintype "passive"))
      (node (ref "SB29") (pin "1") (pinfunction "1_1") (pintype "passive"))
      (node (ref "SB30") (pin "1") (pinfunction "1_1") (pintype "passive"))
    )
    (net (code "70") (name "/T_DBG_RST") (class "Default")
      (node (ref "SB29") (pin "2") (pinfunction "2_2") (pintype "passive"))
    )
    (net (code "71") (name "/USB_FS_N") (class "Default")
      (node (ref "CN2") (pin "18") (pinfunction "18_18") (pintype "passive"))
      (node (ref "CN4") (pin "14") (pinfunction "14_14") (pintype "passive"))
      (node (ref "SB14") (pin "1") (pinfunction "1_1") (pintype "passive"))
    )
    (net (code "72") (name "/USB_FS_P") (class "Default")
      (node (ref "CN2") (pin "16") (pinfunction "16_16") (pintype "passive"))
      (node (ref "CN4") (pin "12") (pinfunction "12_12") (pintype "passive"))
      (node (ref "SB16") (pin "1") (pinfunction "1_1") (pintype "passive"))
    )
    (net (code "73") (name "/USB_N") (class "Default")
      (node (ref "SB14") (pin "2") (pinfunction "2_2") (pintype "passive"))
    )
    (net (code "74") (name "/USB_P") (class "Default")
      (node (ref "SB16") (pin "2") (pinfunction "2_2") (pintype "passive"))
    )
    (net (code "75") (name "/VCP1_T_RX") (class "Default")
      (node (ref "SB5") (pin "2") (pinfunction "2_2") (pintype "passive"))
    )
    (net (code "76") (name "/VCP1_T_TX") (class "Default")
      (node (ref "SB3") (pin "2") (pinfunction "2_2") (pintype "passive"))
    )
    (net (code "77") (name "/VCP2_T_CTS") (class "Default")
      (node (ref "SB24") (pin "2") (pinfunction "2_2") (pintype "passive"))
      (node (ref "SB25") (pin "2") (pinfunction "2_2") (pintype "passive"))
      (node (ref "SB27") (pin "2") (pinfunction "2_2") (pintype "passive"))
    )
    (net (code "78") (name "/VCP2_T_RTS") (class "Default")
      (node (ref "SB23") (pin "2") (pinfunction "2_2") (pintype "passive"))
      (node (ref "SB26") (pin "2") (pinfunction "2_2") (pintype "passive"))
    )
    (net (code "79") (name "/VCP2_T_RX") (class "Default")
      (node (ref "SB7") (pin "2") (pinfunction "2_2") (pintype "passive"))
    )
    (net (code "80") (name "/VCP2_T_TX") (class "Default")
      (node (ref "SB8") (pin "2") (pinfunction "2_2") (pintype "passive"))
    )
    (net (code "81") (name "3V3") (class "Default")
      (node (ref "CN3") (pin "16") (pinfunction "16_16") (pintype "passive"))
      (node (ref "CN5") (pin "4") (pinfunction "4_4") (pintype "passive"))
    )
    (net (code "82") (name "5V") (class "Default")
      (node (ref "CN3") (pin "18") (pinfunction "18_18") (pintype "passive"))
      (node (ref "CN5") (pin "5") (pinfunction "5_5") (pintype "passive"))
    )
    (net (code "83") (name "5V_EXT") (class "Default")
      (node (ref "CN3") (pin "6") (pinfunction "6_6") (pintype "passive"))
    )
    (net (code "84") (name "5V_INT") (class "Default")
      (node (ref "R1") (pin "2") (pinfunction "2_2") (pintype "passive"))
    )
    (net (code "85") (name "5V_USB_MCU") (class "Default")
      (node (ref "CN4") (pin "8") (pinfunction "8_8") (pintype "passive"))
    )
    (net (code "86") (name "GND") (class "Default")
      (node (ref "C1") (pin "1") (pinfunction "1_1") (pintype "passive"))
      (node (ref "C10") (pin "1") (pinfunction "1_1") (pintype "passive"))
      (node (ref "C11") (pin "1") (pinfunction "1_1") (pintype "passive"))
      (node (ref "C2") (pin "1") (pinfunction "1_1") (pintype "passive"))
      (node (ref "C3") (pin "1") (pinfunction "1_1") (pintype "passive"))
      (node (ref "C4") (pin "1") (pinfunction "1_1") (pintype "passive"))
      (node (ref "C5") (pin "1") (pinfunction "1_1") (pintype "passive"))
      (node (ref "C6") (pin "1") (pinfunction "1_1") (pintype "passive"))
      (node (ref "C7") (pin "1") (pinfunction "1_1") (pintype "passive"))
      (node (ref "C8") (pin "1") (pinfunction "1_1") (pintype "passive"))
      (node (ref "C9") (pin "1") (pinfunction "1_1") (pintype "passive"))
      (node (ref "CN1") (pin "1") (pinfunction "1_1") (pintype "passive"))
      (node (ref "CN1") (pin "14") (pinfunction "14_14") (pintype "passive"))
      (node (ref "CN1") (pin "17") (pinfunction "17_17") (pintype "passive"))
      (node (ref "CN1") (pin "22") (pinfunction "22_22") (pintype "passive"))
      (node (ref "CN1") (pin "25") (pinfunction "25_25") (pintype "passive"))
      (node (ref "CN1") (pin "28") (pinfunction "28_28") (pintype "passive"))
      (node (ref "CN1") (pin "31") (pinfunction "31_31") (pintype "passive"))
      (node (ref "CN1") (pin "34") (pinfunction "34_34") (pintype "passive"))
      (node (ref "CN1") (pin "37") (pinfunction "37_37") (pintype "passive"))
      (node (ref "CN1") (pin "40") (pinfunction "40_40") (pintype "passive"))
      (node (ref "CN1") (pin "46") (pinfunction "46_46") (pintype "passive"))
      (node (ref "CN1") (pin "49") (pinfunction "49_49") (pintype "passive"))
      (node (ref "CN1") (pin "6") (pinfunction "6_6") (pintype "passive"))
      (node (ref "CN1") (pin "7") (pinfunction "7_7") (pintype "passive"))
      (node (ref "CN11") (pin "2") (pinfunction "2_2") (pintype "passive"))
      (node (ref "CN14") (pin "2") (pinfunction "2_2") (pintype "passive"))
      (node (ref "CN2") (pin "14") (pinfunction "14_14") (pintype "passive"))
      (node (ref "CN2") (pin "2") (pinfunction "2_2") (pintype "passive"))
      (node (ref "CN2") (pin "20") (pinfunction "20_20") (pintype "passive"))
      (node (ref "CN2") (pin "26") (pinfunction "26_26") (pintype "passive"))
      (node (ref "CN2") (pin "32") (pinfunction "32_32") (pintype "passive"))
      (node (ref "CN2") (pin "38") (pinfunction "38_38") (pintype "passive"))
      (node (ref "CN2") (pin "44") (pinfunction "44_44") (pintype "passive"))
      (node (ref "CN2") (pin "50") (pinfunction "50_50") (pintype "passive"))
      (node (ref "CN2") (pin "8") (pinfunction "8_8") (pintype "passive"))
      (node (ref "CN3") (pin "19") (pinfunction "19_19") (pintype "passive"))
      (node (ref "CN3") (pin "20") (pinfunction "20_20") (pintype "passive"))
      (node (ref "CN3") (pin "22") (pinfunction "22_22") (pintype "passive"))
      (node (ref "CN3") (pin "8") (pinfunction "8_8") (pintype "passive"))
      (node (ref "CN4") (pin "20") (pinfunction "20_20") (pintype "passive"))
      (node (ref "CN4") (pin "32") (pinfunction "32_32") (pintype "passive"))
      (node (ref "CN4") (pin "9") (pinfunction "9_9") (pintype "passive"))
      (node (ref "CN5") (pin "6") (pinfunction "6_6") (pintype "passive"))
      (node (ref "CN5") (pin "7") (pinfunction "7_7") (pintype "passive"))
      (node (ref "CN6") (pin "7") (pinfunction "7_7") (pintype "passive"))
    )
    (net (code "87") (name "Net-(CN3-Pad10)") (class "Default")
      (node (ref "CN3") (pin "10") (pinfunction "10_10") (pintype "passive"))
      (node (ref "R1") (pin "1") (pinfunction "1_1") (pintype "passive"))
    )
    (net (code "88") (name "VBAT") (class "Default")
      (node (ref "CN1") (pin "43") (pinfunction "43_43") (pintype "passive"))
      (node (ref "CN14") (pin "1") (pinfunction "1_1") (pintype "passive"))
      (node (ref "CN3") (pin "33") (pinfunction "33_33") (pintype "passive"))
    )
    (net (code "89") (name "VDD") (class "Default")
      (node (ref "C10") (pin "2") (pinfunction "2_2") (pintype "passive"))
      (node (ref "C11") (pin "2") (pinfunction "2_2") (pintype "passive"))
      (node (ref "C2") (pin "2") (pinfunction "2_2") (pintype "passive"))
      (node (ref "C3") (pin "2") (pinfunction "2_2") (pintype "passive"))
      (node (ref "C4") (pin "2") (pinfunction "2_2") (pintype "passive"))
      (node (ref "C5") (pin "2") (pinfunction "2_2") (pintype "passive"))
      (node (ref "C6") (pin "2") (pinfunction "2_2") (pintype "passive"))
      (node (ref "C7") (pin "2") (pinfunction "2_2") (pintype "passive"))
      (node (ref "C8") (pin "2") (pinfunction "2_2") (pintype "passive"))
      (node (ref "C9") (pin "2") (pinfunction "2_2") (pintype "passive"))
      (node (ref "CN1") (pin "11") (pinfunction "11_11") (pintype "passive"))
      (node (ref "CN1") (pin "18") (pinfunction "18_18") (pintype "passive"))
      (node (ref "CN1") (pin "2") (pinfunction "2_2") (pintype "passive"))
      (node (ref "CN1") (pin "30") (pinfunction "30_30") (pintype "passive"))
      (node (ref "CN1") (pin "32") (pinfunction "32_32") (pintype "passive"))
      (node (ref "CN1") (pin "48") (pinfunction "48_48") (pintype "passive"))
      (node (ref "CN1") (pin "50") (pinfunction "50_50") (pintype "passive"))
      (node (ref "CN2") (pin "1") (pinfunction "1_1") (pintype "passive"))
      (node (ref "CN2") (pin "17") (pinfunction "17_17") (pintype "passive"))
      (node (ref "CN2") (pin "3") (pinfunction "3_3") (pintype "passive"))
      (node (ref "CN2") (pin "31") (pinfunction "31_31") (pintype "passive"))
      (node (ref "CN2") (pin "33") (pinfunction "33_33") (pintype "passive"))
      (node (ref "CN2") (pin "47") (pinfunction "47_47") (pintype "passive"))
      (node (ref "CN2") (pin "49") (pinfunction "49_49") (pintype "passive"))
      (node (ref "CN3") (pin "5") (pinfunction "5_5") (pintype "passive"))
      (node (ref "SB1") (pin "1") (pinfunction "1_1") (pintype "passive"))
    )
    (net (code "90") (name "VDDA") (class "Default")
      (node (ref "C1") (pin "2") (pinfunction "2_2") (pintype "passive"))
      (node (ref "CN1") (pin "20") (pinfunction "20_20") (pintype "passive"))
      (node (ref "CN11") (pin "1") (pinfunction "1_1") (pintype "passive"))
      (node (ref "CN2") (pin "19") (pinfunction "19_19") (pintype "passive"))
      (node (ref "CN4") (pin "7") (pinfunction "7_7") (pintype "passive"))
      (node (ref "CN6") (pin "8") (pinfunction "8_8") (pintype "passive"))
      (node (ref "SB1") (pin "2") (pinfunction "2_2") (pintype "passive"))
    )
    (net (code "91") (name "VIN") (class "Default")
      (node (ref "CN3") (pin "24") (pinfunction "24_24") (pintype "passive"))
      (node (ref "CN5") (pin "8") (pinfunction "8_8") (pintype "passive"))
    )
    (net (code "92") (name "V_TARGET") (class "Default")
      (node (ref "CN1") (pin "4") (pinfunction "4_4") (pintype "passive"))
      (node (ref "CN3") (pin "12") (pinfunction "12_12") (pintype "passive"))
      (node (ref "CN5") (pin "2") (pinfunction "2_2") (pintype "passive"))
    )
    (net (code "93") (name "unconnected-(CN5-Pad1)") (class "Default")
      (node (ref "CN5") (pin "1") (pinfunction "1_1") (pintype "passive+no_connect"))
    )
  )
)
